# main.net
KiCad netlist of a schematic drawn in Altium Designer
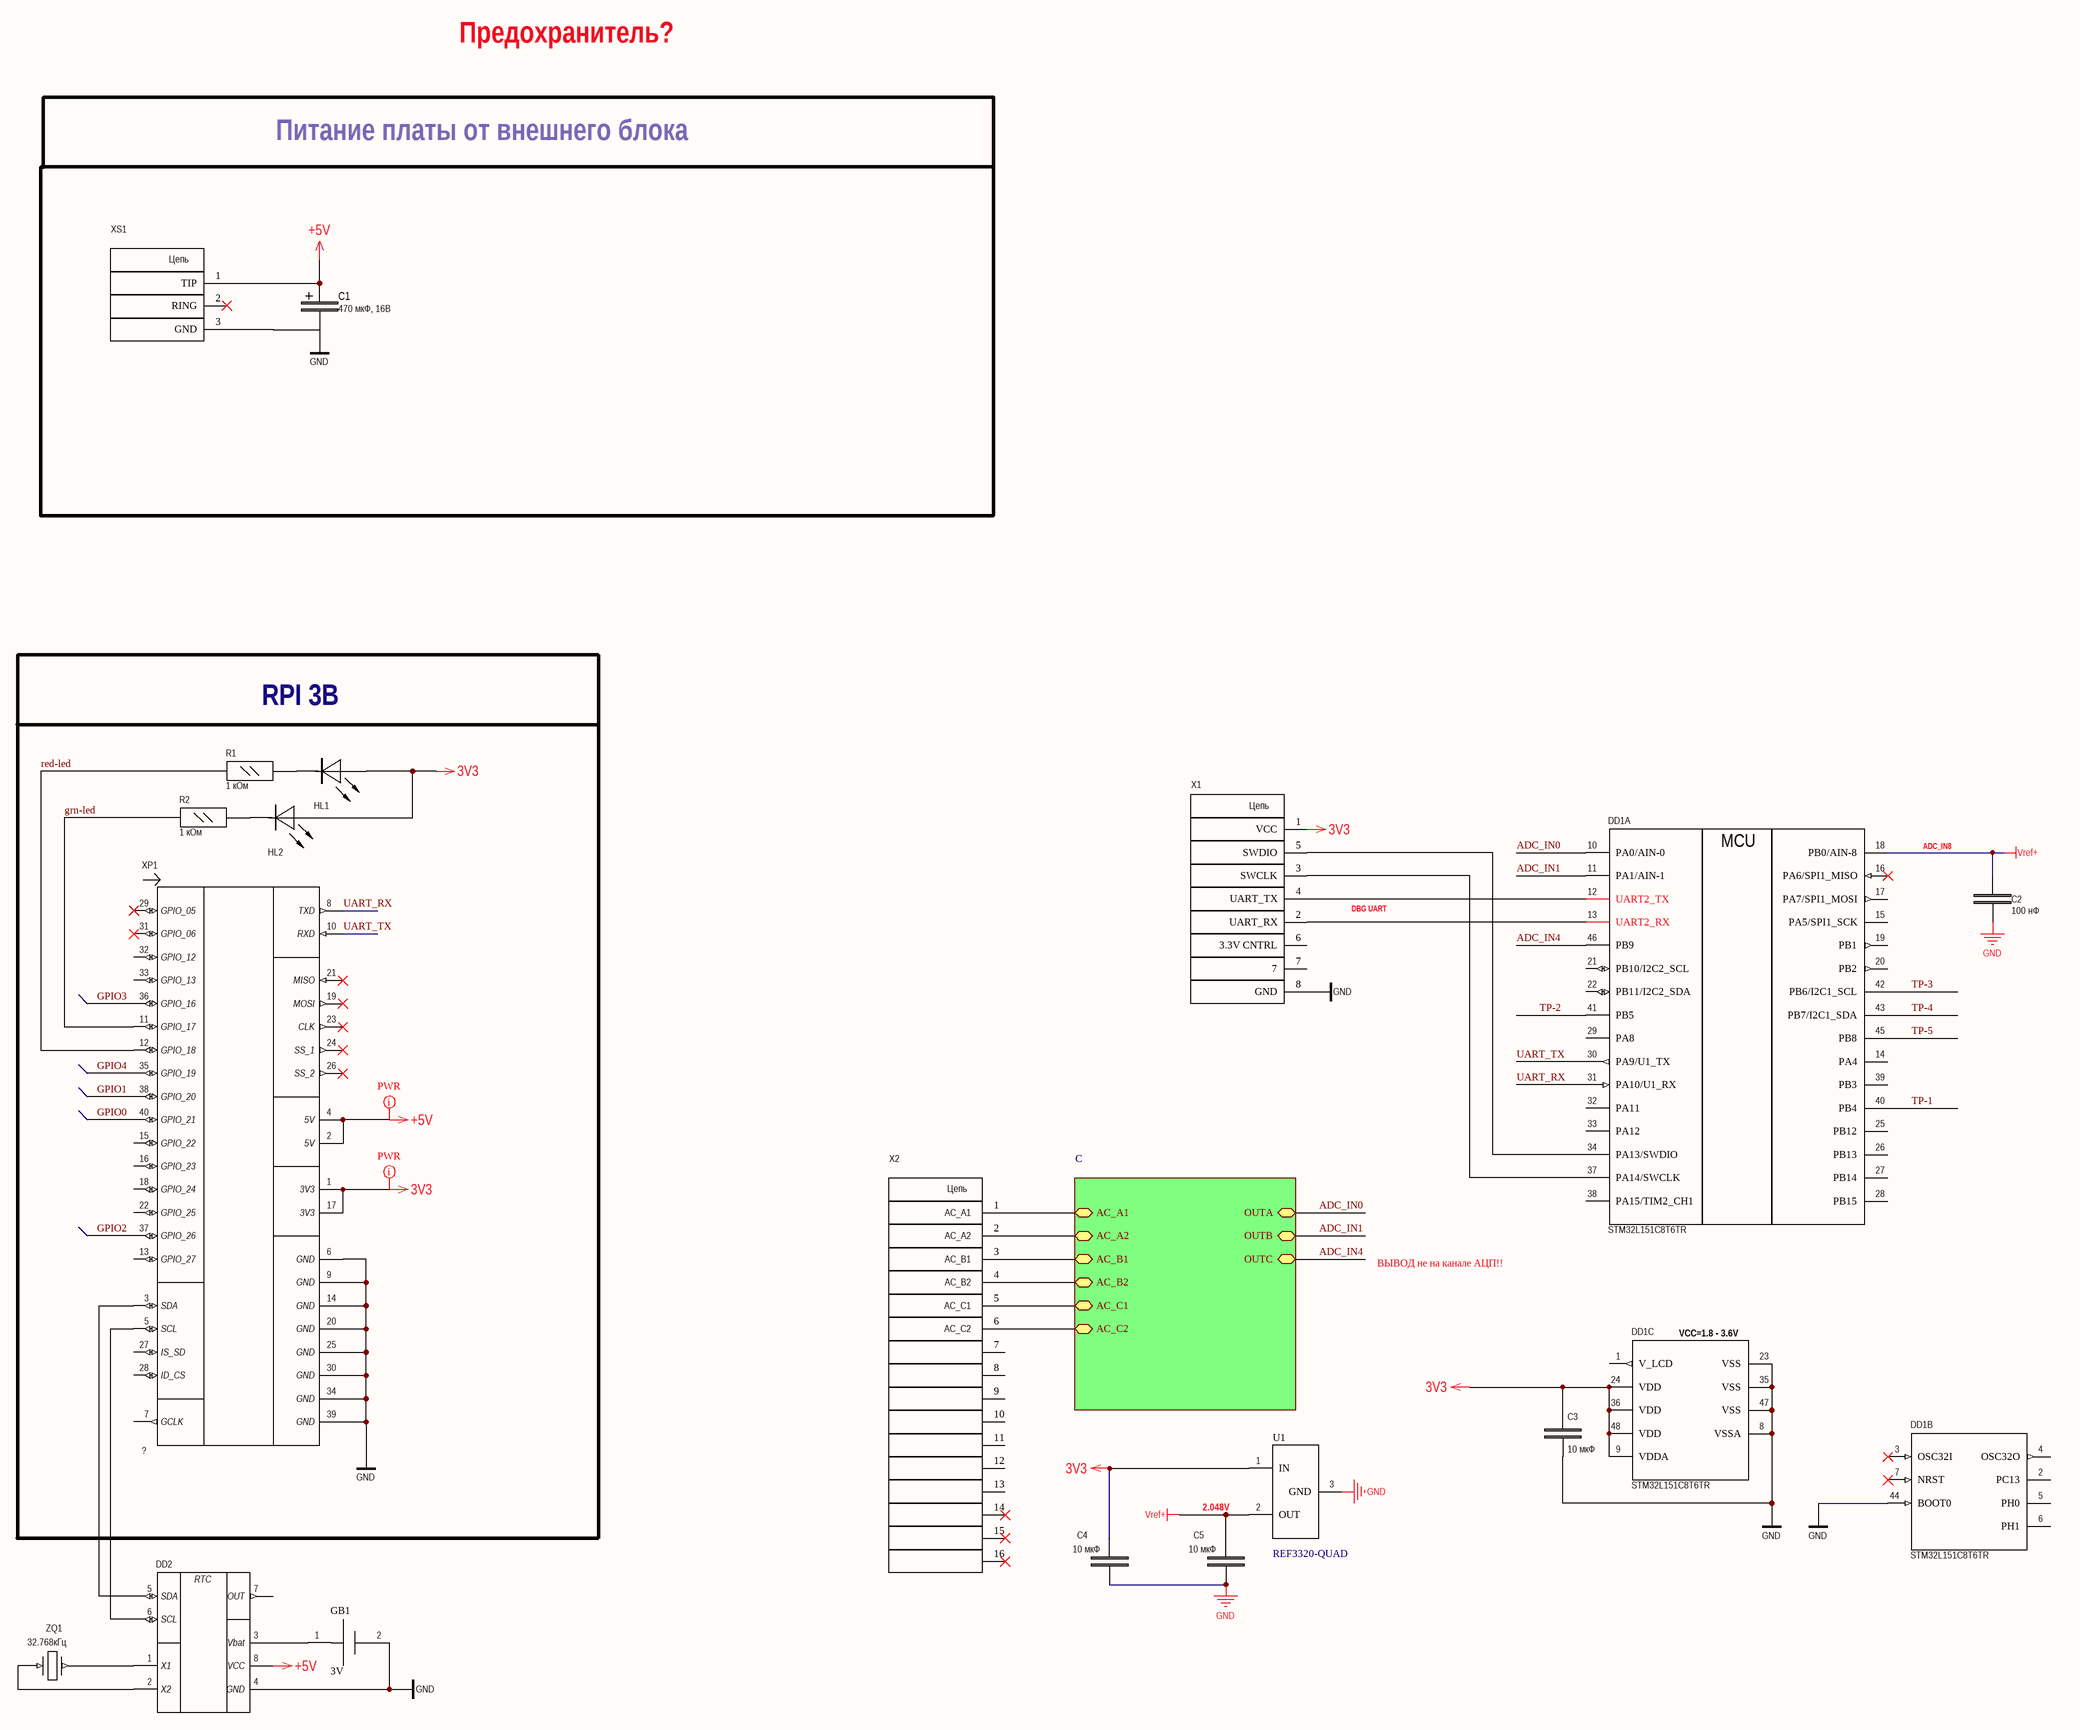
[diagram p0: main.SchDoc]

(export (version "E")
  (design (tool "Eeschema 10.0.6"))
  (components
    (comp (ref "C1")
      (value "470 мкФ, 16В")
      (footprint "ECAP 10x10.5 SMD")
      (libsource (lib "Passive") (part "Конденсатор_полярный"))
    )
    (comp (ref "C2")
      (value "100 нФ")
      (footprint "CAP0402")
      (description "Конденсатор")
      (libsource (lib "Passive") (part "CAP0805"))
    )
    (comp (ref "C3")
      (value "10 мкФ")
      (footprint "CAP0805")
      (description "Конденсатор")
      (libsource (lib "Passive") (part "CAP0805"))
    )
    (comp (ref "C4") (value "10 мкФ") (footprint "CAP0805") (libsource (lib "Passive") (part "CAP0805")))
    (comp (ref "C5") (value "10 мкФ") (footprint "CAP0805") (libsource (lib "Passive") (part "CAP0805")))
    (comp (ref "DD1")
      (value "STM32L151C8T6TR")
      (footprint "LQFP-48")
      (description "Микроконтроллер")
      (libsource (lib "") (part "STM32L151C8T6TR_1"))
    )
    (comp (ref "DD2")
      (value "?")
      (footprint "So-8")
      (description "I2C Real-Time Clock")
      (libsource (lib "IC") (part "DS1307"))
    )
    (comp (ref "GB1")
      (value "3V")
      (footprint "CRC2032 BAT holder")
      (libsource (lib "Connectors") (part "CRC2032 Bat holder"))
    )
    (comp (ref "HL1")
      (value "LED")
      (footprint "LED 3MM R RED")
      (description "Светодиод зеленый")
      (libsource (lib "Semiconductor") (part "LED"))
    )
    (comp (ref "HL2")
      (value "LED")
      (footprint "LED 3MM R GREEN")
      (description "Светодиод красный")
      (libsource (lib "Semiconductor") (part "LED"))
    )
    (comp (ref "R1")
      (value "1 кОм")
      (footprint "RES0402")
      (description "Резистор 0805")
      (fields (field (name "Comment") "RES0805"))
      (libsource (lib "Passive") (part "RES0805"))
    )
    (comp (ref "R2")
      (value "1 кОм")
      (footprint "RES0402")
      (description "Резистор 0805")
      (fields (field (name "Comment") "RES0805"))
      (libsource (lib "Passive") (part "RES0805"))
    )
    (comp (ref "U1")
      (value "REF3320-QUAD")
      (footprint "SOT-23-3v2")
      (libsource (lib "IC") (part "REF3333-QUAD"))
    )
    (comp (ref "X1")
      (value "?")
      (footprint "PBD-08 - POGO PIN")
      (libsource (lib "Connectors") (part "Разьем_8_под_pogopin"))
    )
    (comp (ref "X2")
      (value "?")
      (footprint "microfit30_16")
      (libsource (lib "Connectors") (part "IDC-16-MR"))
    )
    (comp (ref "XP1")
      (value "?")
      (footprint "PBD-40 2.54 RPI")
      (libsource (lib "Connectors") (part "Raspberry Pi 3 Header"))
    )
    (comp (ref "XS1")
      (value "Гнездо питания DS-210")
      (footprint "DS-210")
      (description "2.5x5.5мм")
      (libsource (lib "Connectors") (part "Гнездо питания DC005 5.5x2.5"))
    )
    (comp (ref "ZQ1")
      (value "32.768кГц")
      (footprint "Crystal_1_V1")
      (description "Кварцевый резонатор")
      (libsource (lib "Generators") (part "32.768 кГц"))
    )
  )
  (nets
    (net (code "1") (name "+5V") (class "Default")
      (node (ref "C1") (pin "1") (pinfunction "1_1") (pintype "passive"))
      (node (ref "DD2") (pin "8") (pinfunction "VCC_8") (pintype "power_in"))
      (node (ref "XP1") (pin "2") (pinfunction "5V_2") (pintype "power_in"))
      (node (ref "XP1") (pin "4") (pinfunction "5V_4") (pintype "power_in"))
      (node (ref "XS1") (pin "1") (pinfunction "TIP_1") (pintype "passive"))
    )
    (net (code "2") (name "/AC_A1") (class "Default")
      (node (ref "X2") (pin "1") (pinfunction "AC_A1_1") (pintype "passive"))
    )
    (net (code "3") (name "/AC_A2") (class "Default")
      (node (ref "X2") (pin "2") (pinfunction "AC_A2_2") (pintype "passive"))
    )
    (net (code "4") (name "/AC_B1") (class "Default")
      (node (ref "X2") (pin "3") (pinfunction "AC_B1_3") (pintype "passive"))
    )
    (net (code "5") (name "/AC_B2") (class "Default")
      (node (ref "X2") (pin "4") (pinfunction "AC_B2_4") (pintype "passive"))
    )
    (net (code "6") (name "/AC_C1") (class "Default")
      (node (ref "X2") (pin "5") (pinfunction "AC_C1_5") (pintype "passive"))
    )
    (net (code "7") (name "/AC_C2") (class "Default")
      (node (ref "X2") (pin "6") (pinfunction "AC_C2_6") (pintype "passive"))
    )
    (net (code "8") (name "/ADC_IN0") (class "Default")
      (node (ref "DD1") (pin "10") (pinfunction "PA0/AIN-0_10") (pintype "passive"))
    )
    (net (code "9") (name "/ADC_IN1") (class "Default")
      (node (ref "DD1") (pin "11") (pinfunction "PA1/AIN-1_11") (pintype "passive"))
    )
    (net (code "10") (name "/ADC_IN4") (class "Default")
      (node (ref "DD1") (pin "46") (pinfunction "PB9_46") (pintype "open_collector"))
    )
    (net (code "11") (name "/GPIO0") (class "Default")
      (node (ref "XP1") (pin "40") (pinfunction "GPIO_21_40") (pintype "bidirectional"))
    )
    (net (code "12") (name "/GPIO1") (class "Default")
      (node (ref "XP1") (pin "38") (pinfunction "GPIO_20_38") (pintype "bidirectional"))
    )
    (net (code "13") (name "/GPIO2") (class "Default")
      (node (ref "XP1") (pin "37") (pinfunction "GPIO_26_37") (pintype "bidirectional"))
    )
    (net (code "14") (name "/GPIO3") (class "Default")
      (node (ref "XP1") (pin "36") (pinfunction "GPIO_16_36") (pintype "bidirectional"))
    )
    (net (code "15") (name "/GPIO4") (class "Default")
      (node (ref "XP1") (pin "35") (pinfunction "GPIO_19_35") (pintype "bidirectional"))
    )
    (net (code "16") (name "/TP-1") (class "Default")
      (node (ref "DD1") (pin "40") (pinfunction "PB4_40") (pintype "passive"))
    )
    (net (code "17") (name "/TP-2") (class "Default")
      (node (ref "DD1") (pin "41") (pinfunction "PB5_41") (pintype "passive"))
    )
    (net (code "18") (name "/TP-3") (class "Default")
      (node (ref "DD1") (pin "42") (pinfunction "PB6/I2C1_SCL_42") (pintype "open_collector"))
    )
    (net (code "19") (name "/TP-4") (class "Default")
      (node (ref "DD1") (pin "43") (pinfunction "PB7/I2C1_SDA_43") (pintype "open_collector"))
    )
    (net (code "20") (name "/TP-5") (class "Default")
      (node (ref "DD1") (pin "45") (pinfunction "PB8_45") (pintype "passive"))
    )
    (net (code "21") (name "/UART_RX") (class "Default")
      (node (ref "DD1") (pin "31") (pinfunction "PA10/U1_RX_31") (pintype "input"))
      (node (ref "XP1") (pin "8") (pinfunction "TXD_8") (pintype "output"))
    )
    (net (code "22") (name "/UART_TX") (class "Default")
      (node (ref "DD1") (pin "30") (pinfunction "PA9/U1_TX_30") (pintype "output"))
      (node (ref "XP1") (pin "10") (pinfunction "RXD_10") (pintype "input"))
    )
    (net (code "23") (name "/grn-led") (class "Default")
      (node (ref "R2") (pin "2") (pintype "passive"))
      (node (ref "XP1") (pin "11") (pinfunction "GPIO_17_11") (pintype "bidirectional"))
    )
    (net (code "24") (name "/red-led") (class "Default")
      (node (ref "R1") (pin "2") (pintype "passive"))
      (node (ref "XP1") (pin "12") (pinfunction "GPIO_18_12") (pintype "bidirectional"))
    )
    (net (code "25") (name "3V3") (class "Default")
      (node (ref "C3") (pin "2") (pinfunction "2_2") (pintype "passive"))
      (node (ref "C4") (pin "2") (pinfunction "2_2") (pintype "passive"))
      (node (ref "DD1") (pin "24") (pinfunction "VDD_24") (pintype "power_in"))
      (node (ref "DD1") (pin "36") (pinfunction "VDD_36") (pintype "power_in"))
      (node (ref "DD1") (pin "48") (pinfunction "VDD_48") (pintype "power_in"))
      (node (ref "DD1") (pin "9") (pinfunction "VDDA_9") (pintype "power_in"))
      (node (ref "HL1") (pin "A") (pinfunction "Anode_A") (pintype "passive"))
      (node (ref "HL2") (pin "A") (pinfunction "Anode_A") (pintype "passive"))
      (node (ref "U1") (pin "1") (pinfunction "IN_1") (pintype "passive"))
      (node (ref "X1") (pin "1") (pinfunction "VCC_1") (pintype "passive"))
      (node (ref "XP1") (pin "1") (pinfunction "3V3_1") (pintype "power_in"))
      (node (ref "XP1") (pin "17") (pinfunction "3V3_17") (pintype "power_in"))
    )
    (net (code "26") (name "GND") (class "Default")
      (node (ref "C1") (pin "2") (pinfunction "2_2") (pintype "passive"))
      (node (ref "C2") (pin "1") (pinfunction "1_1") (pintype "passive"))
      (node (ref "C3") (pin "1") (pinfunction "1_1") (pintype "passive"))
      (node (ref "C4") (pin "1") (pinfunction "1_1") (pintype "passive"))
      (node (ref "C5") (pin "1") (pinfunction "1_1") (pintype "passive"))
      (node (ref "DD1") (pin "23") (pinfunction "VSS_23") (pintype "power_in"))
      (node (ref "DD1") (pin "35") (pinfunction "VSS_35") (pintype "power_in"))
      (node (ref "DD1") (pin "44") (pinfunction "BOOT0_44") (pintype "input"))
      (node (ref "DD1") (pin "47") (pinfunction "VSS_47") (pintype "power_in"))
      (node (ref "DD1") (pin "8") (pinfunction "VSSA_8") (pintype "power_in"))
      (node (ref "DD2") (pin "4") (pinfunction "GND_4") (pintype "power_in"))
      (node (ref "GB1") (pin "2") (pinfunction "minus_2") (pintype "passive"))
      (node (ref "U1") (pin "3") (pinfunction "GND_3") (pintype "passive"))
      (node (ref "X1") (pin "8") (pinfunction "GND_8") (pintype "passive"))
      (node (ref "XP1") (pin "14") (pinfunction "GND_14") (pintype "power_in"))
      (node (ref "XP1") (pin "20") (pinfunction "GND_20") (pintype "power_in"))
      (node (ref "XP1") (pin "25") (pinfunction "GND_25") (pintype "power_in"))
      (node (ref "XP1") (pin "30") (pinfunction "GND_30") (pintype "power_in"))
      (node (ref "XP1") (pin "34") (pinfunction "GND_34") (pintype "power_in"))
      (node (ref "XP1") (pin "39") (pinfunction "GND_39") (pintype "power_in"))
      (node (ref "XP1") (pin "6") (pinfunction "GND_6") (pintype "power_in"))
      (node (ref "XP1") (pin "9") (pinfunction "GND_9") (pintype "power_in"))
      (node (ref "XS1") (pin "3") (pinfunction "GND_3") (pintype "passive"))
    )
    (net (code "27") (name "Net-(DD1A-PA13{slash}SWDIO)") (class "Default")
      (node (ref "DD1") (pin "34") (pinfunction "PA13/SWDIO_34") (pintype "passive"))
      (node (ref "X1") (pin "5") (pinfunction "SWDIO_5") (pintype "passive"))
    )
    (net (code "28") (name "Net-(DD1A-PA14{slash}SWCLK)") (class "Default")
      (node (ref "DD1") (pin "37") (pinfunction "PA14/SWCLK_37") (pintype "passive"))
      (node (ref "X1") (pin "3") (pinfunction "SWCLK_3") (pintype "passive"))
    )
    (net (code "29") (name "Net-(DD1A-UART2_RX)") (class "Default")
      (node (ref "DD1") (pin "13") (pinfunction "UART2_RX_13") (pintype "passive"))
      (node (ref "X1") (pin "2") (pinfunction "UART_RX_2") (pintype "passive"))
    )
    (net (code "30") (name "Net-(DD1A-UART2_TX)") (class "Default")
      (node (ref "DD1") (pin "12") (pinfunction "UART2_TX_12") (pintype "passive"))
      (node (ref "X1") (pin "4") (pinfunction "UART_TX_4") (pintype "passive"))
    )
    (net (code "31") (name "Net-(DD2-SCL)") (class "Default")
      (node (ref "DD2") (pin "6") (pinfunction "SCL_6") (pintype "bidirectional"))
      (node (ref "XP1") (pin "5") (pinfunction "SCL_5") (pintype "bidirectional"))
    )
    (net (code "32") (name "Net-(DD2-SDA)") (class "Default")
      (node (ref "DD2") (pin "5") (pinfunction "SDA_5") (pintype "bidirectional"))
      (node (ref "XP1") (pin "3") (pinfunction "SDA_3") (pintype "bidirectional"))
    )
    (net (code "33") (name "Net-(DD2-Vbat)") (class "Default")
      (node (ref "DD2") (pin "3") (pinfunction "Vbat_3") (pintype "power_in"))
      (node (ref "GB1") (pin "1") (pinfunction "plus_1") (pintype "passive"))
    )
    (net (code "34") (name "Net-(DD2-X1)") (class "Default")
      (node (ref "DD2") (pin "1") (pinfunction "X1_1") (pintype "passive"))
      (node (ref "ZQ1") (pin "1") (pinfunction "1_1") (pintype "output"))
    )
    (net (code "35") (name "Net-(DD2-X2)") (class "Default")
      (node (ref "DD2") (pin "2") (pinfunction "X2_2") (pintype "passive"))
      (node (ref "ZQ1") (pin "2") (pinfunction "2_2") (pintype "input"))
    )
    (net (code "36") (name "Net-(HL1-Cathode)") (class "Default")
      (node (ref "HL1") (pin "C") (pinfunction "Cathode_C") (pintype "passive"))
      (node (ref "R1") (pin "1") (pintype "passive"))
    )
    (net (code "37") (name "Net-(HL2-Cathode)") (class "Default")
      (node (ref "HL2") (pin "C") (pinfunction "Cathode_C") (pintype "passive"))
      (node (ref "R2") (pin "1") (pintype "passive"))
    )
    (net (code "38") (name "Vref+") (class "Default")
      (node (ref "C2") (pin "2") (pinfunction "2_2") (pintype "passive"))
      (node (ref "C5") (pin "2") (pinfunction "2_2") (pintype "passive"))
      (node (ref "DD1") (pin "18") (pinfunction "PB0/AIN-8_18") (pintype "passive"))
      (node (ref "U1") (pin "2") (pinfunction "OUT_2") (pintype "passive"))
    )
    (net (code "39") (name "unconnected-(DD1A-PA4-Pad14)") (class "Default")
      (node (ref "DD1") (pin "14") (pinfunction "PA4_14") (pintype "passive"))
    )
    (net (code "40") (name "unconnected-(DD1A-PA5{slash}SPI1_SCK-Pad15)") (class "Default")
      (node (ref "DD1") (pin "15") (pinfunction "PA5/SPI1_SCK_15") (pintype "passive"))
    )
    (net (code "41") (name "unconnected-(DD1A-PA6{slash}SPI1_MISO-Pad16)") (class "Default")
      (node (ref "DD1") (pin "16") (pinfunction "PA6/SPI1_MISO_16") (pintype "input+no_connect"))
    )
    (net (code "42") (name "unconnected-(DD1A-PA7{slash}SPI1_MOSI-Pad17)") (class "Default")
      (node (ref "DD1") (pin "17") (pinfunction "PA7/SPI1_MOSI_17") (pintype "output"))
    )
    (net (code "43") (name "unconnected-(DD1A-PA8-Pad29)") (class "Default")
      (node (ref "DD1") (pin "29") (pinfunction "PA8_29") (pintype "passive"))
    )
    (net (code "44") (name "unconnected-(DD1A-PA11-Pad32)") (class "Default")
      (node (ref "DD1") (pin "32") (pinfunction "PA11_32") (pintype "passive"))
    )
    (net (code "45") (name "unconnected-(DD1A-PA12-Pad33)") (class "Default")
      (node (ref "DD1") (pin "33") (pinfunction "PA12_33") (pintype "passive"))
    )
    (net (code "46") (name "unconnected-(DD1A-PA15{slash}TIM2_CH1-Pad38)") (class "Default")
      (node (ref "DD1") (pin "38") (pinfunction "PA15/TIM2_CH1_38") (pintype "passive"))
    )
    (net (code "47") (name "unconnected-(DD1A-PB1-Pad19)") (class "Default")
      (node (ref "DD1") (pin "19") (pinfunction "PB1_19") (pintype "output"))
    )
    (net (code "48") (name "unconnected-(DD1A-PB2-Pad20)") (class "Default")
      (node (ref "DD1") (pin "20") (pinfunction "PB2_20") (pintype "output"))
    )
    (net (code "49") (name "unconnected-(DD1A-PB3-Pad39)") (class "Default")
      (node (ref "DD1") (pin "39") (pinfunction "PB3_39") (pintype "passive"))
    )
    (net (code "50") (name "unconnected-(DD1A-PB10{slash}I2C2_SCL-Pad21)") (class "Default")
      (node (ref "DD1") (pin "21") (pinfunction "PB10/I2C2_SCL_21") (pintype "bidirectional"))
    )
    (net (code "51") (name "unconnected-(DD1A-PB11{slash}I2C2_SDA-Pad22)") (class "Default")
      (node (ref "DD1") (pin "22") (pinfunction "PB11/I2C2_SDA_22") (pintype "bidirectional"))
    )
    (net (code "52") (name "unconnected-(DD1A-PB12-Pad25)") (class "Default")
      (node (ref "DD1") (pin "25") (pinfunction "PB12_25") (pintype "passive"))
    )
    (net (code "53") (name "unconnected-(DD1A-PB13-Pad26)") (class "Default")
      (node (ref "DD1") (pin "26") (pinfunction "PB13_26") (pintype "passive"))
    )
    (net (code "54") (name "unconnected-(DD1A-PB14-Pad27)") (class "Default")
      (node (ref "DD1") (pin "27") (pinfunction "PB14_27") (pintype "passive"))
    )
    (net (code "55") (name "unconnected-(DD1A-PB15-Pad28)") (class "Default")
      (node (ref "DD1") (pin "28") (pinfunction "PB15_28") (pintype "passive"))
    )
    (net (code "56") (name "unconnected-(DD1B-NRST-Pad7)") (class "Default")
      (node (ref "DD1") (pin "7") (pinfunction "NRST_7") (pintype "input+no_connect"))
    )
    (net (code "57") (name "unconnected-(DD1B-OSC32I-Pad3)") (class "Default")
      (node (ref "DD1") (pin "3") (pinfunction "OSC32I_3") (pintype "input+no_connect"))
    )
    (net (code "58") (name "unconnected-(DD1B-OSC32O-Pad4)") (class "Default")
      (node (ref "DD1") (pin "4") (pinfunction "OSC32O_4") (pintype "output"))
    )
    (net (code "59") (name "unconnected-(DD1B-PC13-Pad2)") (class "Default")
      (node (ref "DD1") (pin "2") (pinfunction "PC13_2") (pintype "passive"))
    )
    (net (code "60") (name "unconnected-(DD1B-PH0-Pad5)") (class "Default")
      (node (ref "DD1") (pin "5") (pinfunction "PH0_5") (pintype "open_collector"))
    )
    (net (code "61") (name "unconnected-(DD1B-PH1-Pad6)") (class "Default")
      (node (ref "DD1") (pin "6") (pinfunction "PH1_6") (pintype "open_collector"))
    )
    (net (code "62") (name "unconnected-(DD1C-V_LCD-Pad1)") (class "Default")
      (node (ref "DD1") (pin "1") (pinfunction "V_LCD_1") (pintype "output"))
    )
    (net (code "63") (name "unconnected-(DD2-OUT-Pad7)") (class "Default")
      (node (ref "DD2") (pin "7") (pinfunction "OUT_7") (pintype "output"))
    )
    (net (code "64") (name "unconnected-(X1-3.3V_CNTRL-Pad6)") (class "Default")
      (node (ref "X1") (pin "6") (pinfunction "3.3V_CNTRL_6") (pintype "passive"))
    )
    (net (code "65") (name "unconnected-(X1-Pad7)") (class "Default")
      (node (ref "X1") (pin "7") (pinfunction "7_7") (pintype "passive"))
    )
    (net (code "66") (name "unconnected-(X2-Pad7)") (class "Default")
      (node (ref "X2") (pin "7") (pintype "passive"))
    )
    (net (code "67") (name "unconnected-(X2-Pad8)") (class "Default")
      (node (ref "X2") (pin "8") (pintype "passive"))
    )
    (net (code "68") (name "unconnected-(X2-Pad9)") (class "Default")
      (node (ref "X2") (pin "9") (pintype "passive"))
    )
    (net (code "69") (name "unconnected-(X2-Pad10)") (class "Default")
      (node (ref "X2") (pin "10") (pintype "passive"))
    )
    (net (code "70") (name "unconnected-(X2-Pad11)") (class "Default")
      (node (ref "X2") (pin "11") (pintype "passive"))
    )
    (net (code "71") (name "unconnected-(X2-Pad12)") (class "Default")
      (node (ref "X2") (pin "12") (pintype "passive"))
    )
    (net (code "72") (name "unconnected-(X2-Pad13)") (class "Default")
      (node (ref "X2") (pin "13") (pintype "passive"))
    )
    (net (code "73") (name "unconnected-(X2-Pad14)") (class "Default")
      (node (ref "X2") (pin "14") (pintype "passive+no_connect"))
    )
    (net (code "74") (name "unconnected-(X2-Pad15)") (class "Default")
      (node (ref "X2") (pin "15") (pintype "passive+no_connect"))
    )
    (net (code "75") (name "unconnected-(X2-Pad16)") (class "Default")
      (node (ref "X2") (pin "16") (pintype "passive+no_connect"))
    )
    (net (code "76") (name "unconnected-(XP1-CLK-Pad23)") (class "Default")
      (node (ref "XP1") (pin "23") (pinfunction "CLK_23") (pintype "output+no_connect"))
    )
    (net (code "77") (name "unconnected-(XP1-GCLK-Pad7)") (class "Default")
      (node (ref "XP1") (pin "7") (pinfunction "GCLK_7") (pintype "output"))
    )
    (net (code "78") (name "unconnected-(XP1-GPIO_05-Pad29)") (class "Default")
      (node (ref "XP1") (pin "29") (pinfunction "GPIO_05_29") (pintype "bidirectional+no_connect"))
    )
    (net (code "79") (name "unconnected-(XP1-GPIO_06-Pad31)") (class "Default")
      (node (ref "XP1") (pin "31") (pinfunction "GPIO_06_31") (pintype "bidirectional+no_connect"))
    )
    (net (code "80") (name "unconnected-(XP1-GPIO_12-Pad32)") (class "Default")
      (node (ref "XP1") (pin "32") (pinfunction "GPIO_12_32") (pintype "bidirectional"))
    )
    (net (code "81") (name "unconnected-(XP1-GPIO_13-Pad33)") (class "Default")
      (node (ref "XP1") (pin "33") (pinfunction "GPIO_13_33") (pintype "bidirectional"))
    )
    (net (code "82") (name "unconnected-(XP1-GPIO_22-Pad15)") (class "Default")
      (node (ref "XP1") (pin "15") (pinfunction "GPIO_22_15") (pintype "bidirectional"))
    )
    (net (code "83") (name "unconnected-(XP1-GPIO_23-Pad16)") (class "Default")
      (node (ref "XP1") (pin "16") (pinfunction "GPIO_23_16") (pintype "bidirectional"))
    )
    (net (code "84") (name "unconnected-(XP1-GPIO_24-Pad18)") (class "Default")
      (node (ref "XP1") (pin "18") (pinfunction "GPIO_24_18") (pintype "bidirectional"))
    )
    (net (code "85") (name "unconnected-(XP1-GPIO_25-Pad22)") (class "Default")
      (node (ref "XP1") (pin "22") (pinfunction "GPIO_25_22") (pintype "bidirectional"))
    )
    (net (code "86") (name "unconnected-(XP1-GPIO_27-Pad13)") (class "Default")
      (node (ref "XP1") (pin "13") (pinfunction "GPIO_27_13") (pintype "bidirectional"))
    )
    (net (code "87") (name "unconnected-(XP1-ID_CS-Pad28)") (class "Default")
      (node (ref "XP1") (pin "28") (pinfunction "ID_CS_28") (pintype "bidirectional"))
    )
    (net (code "88") (name "unconnected-(XP1-IS_SD-Pad27)") (class "Default")
      (node (ref "XP1") (pin "27") (pinfunction "IS_SD_27") (pintype "bidirectional"))
    )
    (net (code "89") (name "unconnected-(XP1-MISO-Pad21)") (class "Default")
      (node (ref "XP1") (pin "21") (pinfunction "MISO_21") (pintype "input+no_connect"))
    )
    (net (code "90") (name "unconnected-(XP1-MOSI-Pad19)") (class "Default")
      (node (ref "XP1") (pin "19") (pinfunction "MOSI_19") (pintype "output+no_connect"))
    )
    (net (code "91") (name "unconnected-(XP1-SS_1-Pad24)") (class "Default")
      (node (ref "XP1") (pin "24") (pinfunction "SS_1_24") (pintype "output+no_connect"))
    )
    (net (code "92") (name "unconnected-(XP1-SS_2-Pad26)") (class "Default")
      (node (ref "XP1") (pin "26") (pinfunction "SS_2_26") (pintype "output+no_connect"))
    )
    (net (code "93") (name "unconnected-(XS1-RING-Pad2)") (class "Default")
      (node (ref "XS1") (pin "2") (pinfunction "RING_2") (pintype "passive+no_connect"))
    )
  )
)
